# 1_power.net
KiCad netlist of a schematic drawn in Altium Designer
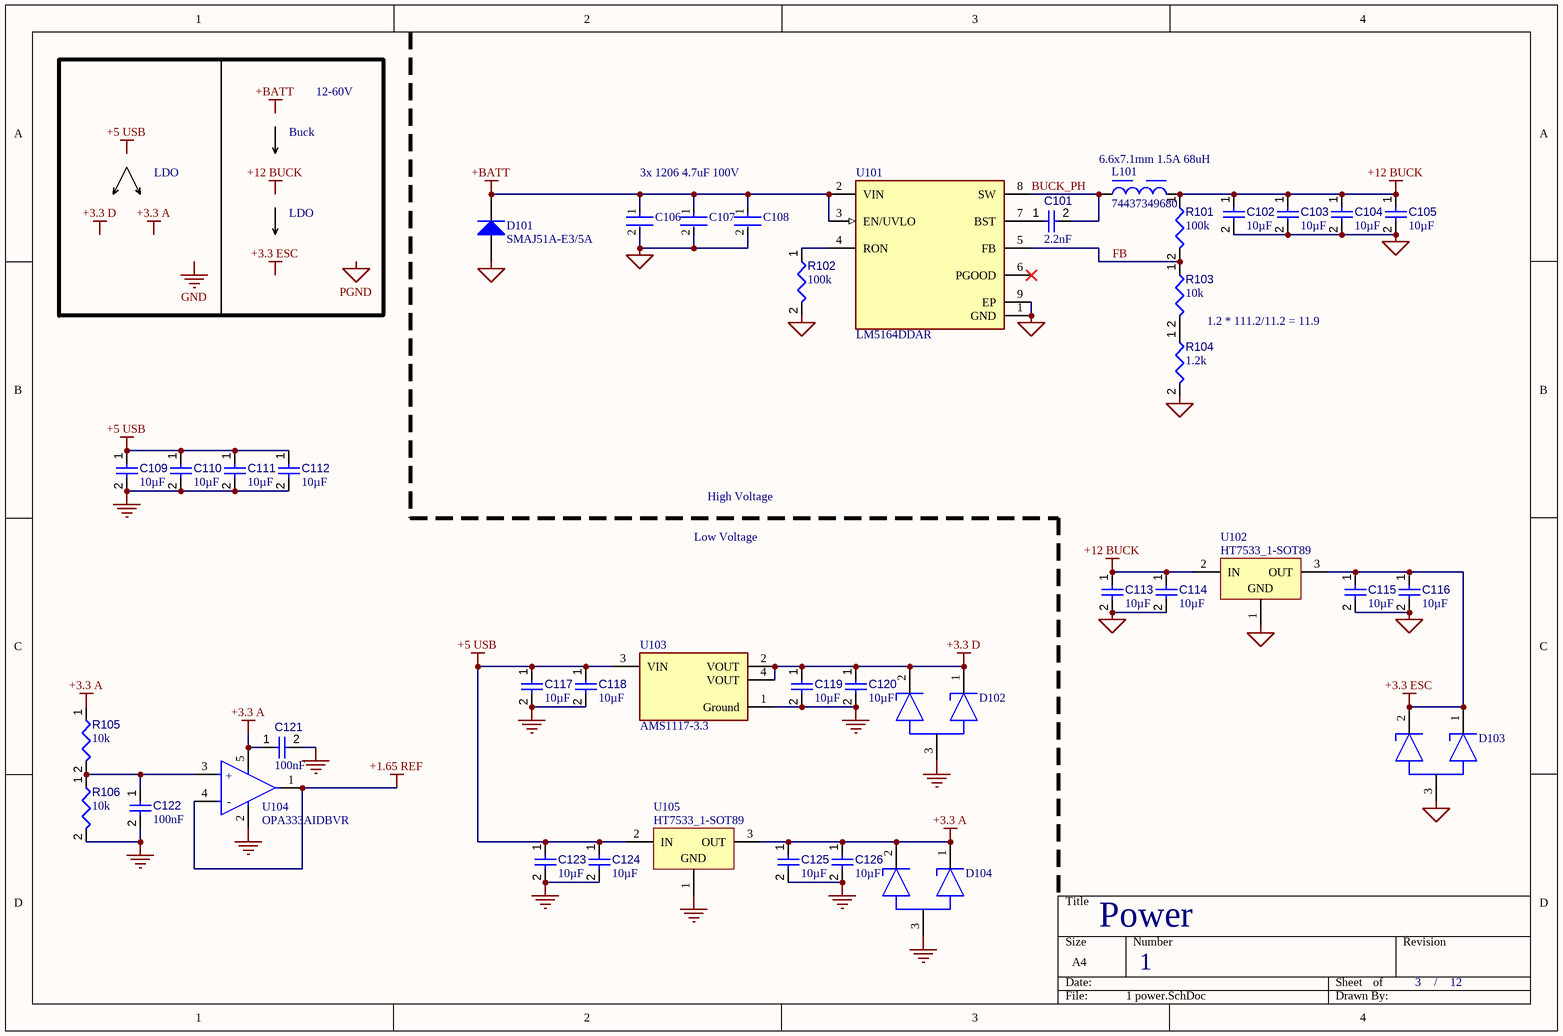
[diagram p0: 1 power.SchDoc]

(export (version "E")
  (design (tool "Eeschema 10.0.6"))
  (components
    (comp (ref "C101")
      (value "2.2nF")
      (footprint "CAPC0402(1005)33_L")
      (description "Chip Capacitor, 1nF +/-20%, 50V, 0402, Thickness 0.33 mm")
      (fields (field (name "TOLERANCE") "10%") (field (name "Comment") "Capacitor 2.2nF +/-20% 50V 0402"))
      (libsource (lib "UBC Uncrewed Aircraft Systems") (part "CAP-NP-2"))
    )
    (comp (ref "C102")
      (value "10µF")
      (footprint "CAPC0603(1608)100_L")
      (description "Chip Capacitor, 10µF +/-20%, 10V, 0603, Thickness 1 mm")
      (fields (field (name "TOLERANCE") "10%") (field (name "Comment") "Capacitor 10µF +/-20% 10V 0603"))
      (libsource (lib "UBC Uncrewed Aircraft Systems") (part "CAP-NP-2"))
    )
    (comp (ref "C103")
      (value "10µF")
      (footprint "CAPC0603(1608)100_L")
      (description "Chip Capacitor, 10µF +/-20%, 10V, 0603, Thickness 1 mm")
      (fields (field (name "TOLERANCE") "10%") (field (name "Comment") "Capacitor 10µF +/-20% 10V 0603"))
      (libsource (lib "UBC Uncrewed Aircraft Systems") (part "CAP-NP-2"))
    )
    (comp (ref "C104")
      (value "10µF")
      (footprint "CAPC0603(1608)100_L")
      (description "Chip Capacitor, 10µF +/-20%, 10V, 0603, Thickness 1 mm")
      (fields (field (name "TOLERANCE") "10%") (field (name "Comment") "Capacitor 10µF +/-20% 10V 0603"))
      (libsource (lib "UBC Uncrewed Aircraft Systems") (part "CAP-NP-2"))
    )
    (comp (ref "C105")
      (value "10µF")
      (footprint "CAPC0603(1608)100_L")
      (description "Chip Capacitor, 10µF +/-20%, 10V, 0603, Thickness 1 mm")
      (fields (field (name "TOLERANCE") "10%") (field (name "Comment") "Capacitor 10µF +/-20% 10V 0603"))
      (libsource (lib "UBC Uncrewed Aircraft Systems") (part "CAP-NP-2"))
    )
    (comp (ref "C106")
      (value "12061Z475KAT2A")
      (footprint "FP-1206-L_3_2_0_2-W_1_6_0-MFG")
      (description "CAP CER 4.7UF 100V X7S 1206")
      (fields (field (name "TOLERANCE") "10%"))
      (libsource (lib "Altium Content Vault") (part "b4654b650e69147ec39a6b967a45e02"))
    )
    (comp (ref "C107")
      (value "12061Z475KAT2A")
      (footprint "FP-1206-L_3_2_0_2-W_1_6_0-MFG")
      (description "CAP CER 4.7UF 100V X7S 1206")
      (fields (field (name "TOLERANCE") "10%"))
      (libsource (lib "Altium Content Vault") (part "b4654b650e69147ec39a6b967a45e02"))
    )
    (comp (ref "C108")
      (value "12061Z475KAT2A")
      (footprint "FP-1206-L_3_2_0_2-W_1_6_0-MFG")
      (description "CAP CER 4.7UF 100V X7S 1206")
      (fields (field (name "TOLERANCE") "10%"))
      (libsource (lib "Altium Content Vault") (part "b4654b650e69147ec39a6b967a45e02"))
    )
    (comp (ref "C109")
      (value "10µF")
      (footprint "CAPC0603(1608)100_L")
      (description "Chip Capacitor, 10µF +/-20%, 10V, 0603, Thickness 1 mm")
      (fields (field (name "TOLERANCE") "10%") (field (name "Comment") "Capacitor 10µF +/-20% 10V 0603"))
      (libsource (lib "UBC Uncrewed Aircraft Systems") (part "CAP-NP-2"))
    )
    (comp (ref "C110")
      (value "10µF")
      (footprint "CAPC0603(1608)100_L")
      (description "Chip Capacitor, 10µF +/-20%, 10V, 0603, Thickness 1 mm")
      (fields (field (name "TOLERANCE") "10%") (field (name "Comment") "Capacitor 10µF +/-20% 10V 0603"))
      (libsource (lib "UBC Uncrewed Aircraft Systems") (part "CAP-NP-2"))
    )
    (comp (ref "C111")
      (value "10µF")
      (footprint "CAPC0603(1608)100_L")
      (description "Chip Capacitor, 10µF +/-20%, 10V, 0603, Thickness 1 mm")
      (fields (field (name "TOLERANCE") "10%") (field (name "Comment") "Capacitor 10µF +/-20% 10V 0603"))
      (libsource (lib "UBC Uncrewed Aircraft Systems") (part "CAP-NP-2"))
    )
    (comp (ref "C112")
      (value "10µF")
      (footprint "CAPC0603(1608)100_L")
      (description "Chip Capacitor, 10µF +/-20%, 10V, 0603, Thickness 1 mm")
      (fields (field (name "TOLERANCE") "10%") (field (name "Comment") "Capacitor 10µF +/-20% 10V 0603"))
      (libsource (lib "UBC Uncrewed Aircraft Systems") (part "CAP-NP-2"))
    )
    (comp (ref "C113")
      (value "10µF")
      (footprint "CAPC0603(1608)100_L")
      (description "Chip Capacitor, 10µF +/-20%, 10V, 0603, Thickness 1 mm")
      (fields (field (name "TOLERANCE") "10%") (field (name "Comment") "Capacitor 10µF +/-20% 10V 0603"))
      (libsource (lib "UBC Uncrewed Aircraft Systems") (part "CAP-NP-2"))
    )
    (comp (ref "C114")
      (value "10µF")
      (footprint "CAPC0603(1608)100_L")
      (description "Chip Capacitor, 10µF +/-20%, 10V, 0603, Thickness 1 mm")
      (fields (field (name "TOLERANCE") "10%") (field (name "Comment") "Capacitor 10µF +/-20% 10V 0603"))
      (libsource (lib "UBC Uncrewed Aircraft Systems") (part "CAP-NP-2"))
    )
    (comp (ref "C115")
      (value "10µF")
      (footprint "CAPC0603(1608)100_L")
      (description "Chip Capacitor, 10µF +/-20%, 10V, 0603, Thickness 1 mm")
      (fields (field (name "TOLERANCE") "10%") (field (name "Comment") "Capacitor 10µF +/-20% 10V 0603"))
      (libsource (lib "UBC Uncrewed Aircraft Systems") (part "CAP-NP-2"))
    )
    (comp (ref "C116")
      (value "10µF")
      (footprint "CAPC0603(1608)100_L")
      (description "Chip Capacitor, 10µF +/-20%, 10V, 0603, Thickness 1 mm")
      (fields (field (name "TOLERANCE") "10%") (field (name "Comment") "Capacitor 10µF +/-20% 10V 0603"))
      (libsource (lib "UBC Uncrewed Aircraft Systems") (part "CAP-NP-2"))
    )
    (comp (ref "C117")
      (value "10µF")
      (footprint "CAPC0603(1608)100_L")
      (description "Chip Capacitor, 10µF +/-20%, 10V, 0603, Thickness 1 mm")
      (fields (field (name "TOLERANCE") "10%") (field (name "Comment") "Capacitor 10µF +/-20% 10V 0603"))
      (libsource (lib "UBC Uncrewed Aircraft Systems") (part "CAP-NP-2"))
    )
    (comp (ref "C118")
      (value "10µF")
      (footprint "CAPC0603(1608)100_L")
      (description "Chip Capacitor, 10µF +/-20%, 10V, 0603, Thickness 1 mm")
      (fields (field (name "TOLERANCE") "10%") (field (name "Comment") "Capacitor 10µF +/-20% 10V 0603"))
      (libsource (lib "UBC Uncrewed Aircraft Systems") (part "CAP-NP-2"))
    )
    (comp (ref "C119")
      (value "10µF")
      (footprint "CAPC0603(1608)100_L")
      (description "Chip Capacitor, 10µF +/-20%, 10V, 0603, Thickness 1 mm")
      (fields (field (name "TOLERANCE") "10%") (field (name "Comment") "Capacitor 10µF +/-20% 10V 0603"))
      (libsource (lib "UBC Uncrewed Aircraft Systems") (part "CAP-NP-2"))
    )
    (comp (ref "C120")
      (value "10µF")
      (footprint "CAPC0603(1608)100_L")
      (description "Chip Capacitor, 10µF +/-20%, 10V, 0603, Thickness 1 mm")
      (fields (field (name "TOLERANCE") "10%") (field (name "Comment") "Capacitor 10µF +/-20% 10V 0603"))
      (libsource (lib "UBC Uncrewed Aircraft Systems") (part "CAP-NP-2"))
    )
    (comp (ref "C121")
      (value "100nF")
      (footprint "CAPC0402(1005)60_L")
      (description "Chip Capacitor, 100nF +/-20%, 25V, 0402, Thickness 0.6 mm")
      (fields (field (name "TOLERANCE") "10%") (field (name "Comment") "Capacitor 100nF +/-20% 25V 0402"))
      (libsource (lib "UBC Uncrewed Aircraft Systems") (part "CAP-NP-2"))
    )
    (comp (ref "C122")
      (value "100nF")
      (footprint "CAPC0402(1005)60_L")
      (description "Chip Capacitor, 100nF +/-20%, 25V, 0402, Thickness 0.6 mm")
      (fields (field (name "TOLERANCE") "10%") (field (name "Comment") "Capacitor 100nF +/-20% 25V 0402"))
      (libsource (lib "UBC Uncrewed Aircraft Systems") (part "CAP-NP-2"))
    )
    (comp (ref "C123")
      (value "10µF")
      (footprint "CAPC0603(1608)100_L")
      (description "Chip Capacitor, 10µF +/-20%, 10V, 0603, Thickness 1 mm")
      (fields (field (name "TOLERANCE") "10%") (field (name "Comment") "Capacitor 10µF +/-20% 10V 0603"))
      (libsource (lib "UBC Uncrewed Aircraft Systems") (part "CAP-NP-2"))
    )
    (comp (ref "C124")
      (value "10µF")
      (footprint "CAPC0603(1608)100_L")
      (description "Chip Capacitor, 10µF +/-20%, 10V, 0603, Thickness 1 mm")
      (fields (field (name "TOLERANCE") "10%") (field (name "Comment") "Capacitor 10µF +/-20% 10V 0603"))
      (libsource (lib "UBC Uncrewed Aircraft Systems") (part "CAP-NP-2"))
    )
    (comp (ref "C125")
      (value "10µF")
      (footprint "CAPC0603(1608)100_L")
      (description "Chip Capacitor, 10µF +/-20%, 10V, 0603, Thickness 1 mm")
      (fields (field (name "TOLERANCE") "10%") (field (name "Comment") "Capacitor 10µF +/-20% 10V 0603"))
      (libsource (lib "UBC Uncrewed Aircraft Systems") (part "CAP-NP-2"))
    )
    (comp (ref "C126")
      (value "10µF")
      (footprint "CAPC0603(1608)100_L")
      (description "Chip Capacitor, 10µF +/-20%, 10V, 0603, Thickness 1 mm")
      (fields (field (name "TOLERANCE") "10%") (field (name "Comment") "Capacitor 10µF +/-20% 10V 0603"))
      (libsource (lib "UBC Uncrewed Aircraft Systems") (part "CAP-NP-2"))
    )
    (comp (ref "D101")
      (value "SMAJ51A-E3/5A")
      (footprint "VISH-DO-214AC-2_N")
      (fields (field (name "MANUFACTURER") "Vishay Semiconductor"))
      (libsource (lib "Altium Content Vault") (part "VISH-K1A2-2"))
    )
    (comp (ref "D102")
      (value "PESD3V3S2UT,215")
      (footprint "FP-SOT23-IPC_A")
      (description "TVS DIODE 3.3VWM 20VC TO236AB")
      (libsource (lib "Altium Content Vault") (part "05bab3e457e9f60b0f1ca7a96343362"))
    )
    (comp (ref "D103")
      (value "PESD3V3S2UT,215")
      (footprint "FP-SOT23-IPC_A")
      (description "TVS DIODE 3.3VWM 20VC TO236AB")
      (libsource (lib "Altium Content Vault") (part "05bab3e457e9f60b0f1ca7a96343362"))
    )
    (comp (ref "D104")
      (value "PESD3V3S2UT,215")
      (footprint "FP-SOT23-IPC_A")
      (description "TVS DIODE 3.3VWM 20VC TO236AB")
      (libsource (lib "Altium Content Vault") (part "05bab3e457e9f60b0f1ca7a96343362"))
    )
    (comp (ref "L101")
      (value "74437349680")
      (footprint "WE-LHMI_7050")
      (libsource (lib "Altium Content Vault") (part "Inductor - 3"))
    )
    (comp (ref "R101")
      (value "100k")
      (footprint "RESC0402(1005)_L")
      (description "Chip Resistor, 100 kOhms, +/-1 %, 63 mW, -55 to 155 degC, 0402")
      (fields (field (name "TOLERANCE") "1%") (field (name "POWER") "63mW"))
      (libsource (lib "UBC Uncrewed Aircraft Systems") (part "RES-2"))
    )
    (comp (ref "R102")
      (value "100k")
      (footprint "RESC0402(1005)_L")
      (description "Chip Resistor, 100 kOhms, +/-1 %, 63 mW, -55 to 155 degC, 0402")
      (fields (field (name "TOLERANCE") "1%") (field (name "POWER") "63mW"))
      (libsource (lib "UBC Uncrewed Aircraft Systems") (part "RES-2"))
    )
    (comp (ref "R103")
      (value "10k")
      (footprint "RESC0402(1005)_L")
      (description "Chip Resistor, 10 kOhms, +/-1 %, 63 mW, -55 to 125 degC, 0402")
      (fields (field (name "POWER") "63mW") (field (name "TOLERANCE") "1%"))
      (libsource (lib "UBC Uncrewed Aircraft Systems") (part "RES-2"))
    )
    (comp (ref "R104")
      (value "1.2k")
      (footprint "RESC0402(1005)_L")
      (description "Chip Resistor, 1.2 kOhms, +/-1 %, 63 mW, -55 to 155 degC, 0402")
      (fields (field (name "TOLERANCE") "1%") (field (name "POWER") "63mW"))
      (libsource (lib "UBC Uncrewed Aircraft Systems") (part "RES-2"))
    )
    (comp (ref "R105")
      (value "10k")
      (footprint "RESC0402(1005)_L")
      (description "Chip Resistor, 10 kOhms, +/-1 %, 63 mW, -55 to 125 degC, 0402")
      (fields (field (name "POWER") "63mW") (field (name "TOLERANCE") "1%"))
      (libsource (lib "UBC Uncrewed Aircraft Systems") (part "RES-2"))
    )
    (comp (ref "R106")
      (value "10k")
      (footprint "RESC0402(1005)_L")
      (description "Chip Resistor, 10 kOhms, +/-1 %, 63 mW, -55 to 125 degC, 0402")
      (fields (field (name "POWER") "63mW") (field (name "TOLERANCE") "1%"))
      (libsource (lib "UBC Uncrewed Aircraft Systems") (part "RES-2"))
    )
    (comp (ref "U101")
      (value "LM5164DDAR")
      (footprint "FP-DDA0008E-MFG")
      (description "POWER MANAGEMENT")
      (fields
        (field (name "MANUFACTURER") "Texas Instruments")
        (field (name "OCTOPART") "https://octopart.com/lm5164ddar-texas+instruments-96785744")
      )
      (libsource (lib "Altium Content Vault") (part "ad4762e8767f3654d2dc1ed5c3dee12"))
    )
    (comp (ref "U102")
      (value "HT7533_1-SOT89")
      (footprint "SOT89_L")
      (description "100mA Low Power LDO, Output Voltage 3.3V, SOT89 Pkg")
      (libsource (lib "Altium Content Vault") (part "PM-REG-HT75xx-1-IL3"))
    )
    (comp (ref "U103")
      (value "AMS1117-3.3")
      (footprint "FP-AMS1117-IPC_C")
      (description "LDO Voltage Regulators 1A, 3.3V")
      (fields
        (field (name "OCTOPART") "https://octopart.com/ams1117-3.3-advanced+monolithic+systems-25899300")
        (field (name "MANUFACTURER") "Advanced Monolithic Systems")
      )
      (libsource (lib "Altium Content Vault") (part "8bdbb5f8e77002000e30dd2845d0354"))
    )
    (comp (ref "U104")
      (value "OPA333AIDBVR")
      (footprint "FP-DBV0005A-MFG")
      (description "IC OPAMP ZER-DRIFT 1CIRC SOT23-5")
      (libsource (lib "Altium Content Vault") (part "1dcd28e651784f0a5a8ed6f8452eeff"))
    )
    (comp (ref "U105")
      (value "HT7533_1-SOT89")
      (footprint "SOT89_L")
      (description "100mA Low Power LDO, Output Voltage 3.3V, SOT89 Pkg")
      (libsource (lib "Altium Content Vault") (part "PM-REG-HT75xx-1-IL3"))
    )
  )
  (nets
    (net (code "1") (name "+1.65 REF") (class "Default")
      (node (ref "U104") (pin "1") (pinfunction "OUT_1") (pintype "passive"))
      (node (ref "U104") (pin "4") (pinfunction "-IN_4") (pintype "tri_state"))
    )
    (net (code "2") (name "+3.3 A") (class "Default")
      (node (ref "C121") (pin "1") (pinfunction "1_1") (pintype "passive"))
      (node (ref "C125") (pin "1") (pinfunction "1_1") (pintype "passive"))
      (node (ref "C126") (pin "1") (pinfunction "1_1") (pintype "passive"))
      (node (ref "D104") (pin "1") (pinfunction "1_1") (pintype "passive"))
      (node (ref "D104") (pin "2") (pinfunction "2_2") (pintype "passive"))
      (node (ref "R105") (pin "1") (pinfunction "1_1") (pintype "passive"))
      (node (ref "U104") (pin "5") (pinfunction "V+_5") (pintype "power_in"))
      (node (ref "U105") (pin "3") (pinfunction "OUT_3") (pintype "power_in"))
    )
    (net (code "3") (name "+3.3 D") (class "Default")
      (node (ref "C119") (pin "1") (pinfunction "1_1") (pintype "passive"))
      (node (ref "C120") (pin "1") (pinfunction "1_1") (pintype "passive"))
      (node (ref "D102") (pin "1") (pinfunction "1_1") (pintype "passive"))
      (node (ref "D102") (pin "2") (pinfunction "2_2") (pintype "passive"))
      (node (ref "U103") (pin "2") (pinfunction "VOUT_2") (pintype "passive"))
      (node (ref "U103") (pin "4") (pinfunction "VOUT_4") (pintype "passive"))
    )
    (net (code "4") (name "+3.3 ESC") (class "Default")
      (node (ref "C115") (pin "1") (pinfunction "1_1") (pintype "passive"))
      (node (ref "C116") (pin "1") (pinfunction "1_1") (pintype "passive"))
      (node (ref "D103") (pin "1") (pinfunction "1_1") (pintype "passive"))
      (node (ref "D103") (pin "2") (pinfunction "2_2") (pintype "passive"))
      (node (ref "U102") (pin "3") (pinfunction "OUT_3") (pintype "power_in"))
    )
    (net (code "5") (name "+5 USB") (class "Default")
      (node (ref "C109") (pin "1") (pinfunction "1_1") (pintype "passive"))
      (node (ref "C110") (pin "1") (pinfunction "1_1") (pintype "passive"))
      (node (ref "C111") (pin "1") (pinfunction "1_1") (pintype "passive"))
      (node (ref "C112") (pin "1") (pinfunction "1_1") (pintype "passive"))
      (node (ref "C117") (pin "1") (pinfunction "1_1") (pintype "passive"))
      (node (ref "C118") (pin "1") (pinfunction "1_1") (pintype "passive"))
      (node (ref "C123") (pin "1") (pinfunction "1_1") (pintype "passive"))
      (node (ref "C124") (pin "1") (pinfunction "1_1") (pintype "passive"))
      (node (ref "U103") (pin "3") (pinfunction "VIN_3") (pintype "power_in"))
      (node (ref "U105") (pin "2") (pinfunction "IN_2") (pintype "power_in"))
    )
    (net (code "6") (name "+12 BUCK") (class "Default")
      (node (ref "C102") (pin "1") (pinfunction "1_1") (pintype "passive"))
      (node (ref "C103") (pin "1") (pinfunction "1_1") (pintype "passive"))
      (node (ref "C104") (pin "1") (pinfunction "1_1") (pintype "passive"))
      (node (ref "C105") (pin "1") (pinfunction "1_1") (pintype "passive"))
      (node (ref "C113") (pin "1") (pinfunction "1_1") (pintype "passive"))
      (node (ref "C114") (pin "1") (pinfunction "1_1") (pintype "passive"))
      (node (ref "L101") (pin "2") (pinfunction "2_2") (pintype "passive"))
      (node (ref "R101") (pin "1") (pinfunction "1_1") (pintype "passive"))
      (node (ref "U102") (pin "2") (pinfunction "IN_2") (pintype "power_in"))
    )
    (net (code "7") (name "+BATT") (class "Default")
      (node (ref "C106") (pin "1") (pinfunction "1_1") (pintype "passive"))
      (node (ref "C107") (pin "1") (pinfunction "1_1") (pintype "passive"))
      (node (ref "C108") (pin "1") (pinfunction "1_1") (pintype "passive"))
      (node (ref "D101") (pin "1") (pinfunction "K_1") (pintype "passive"))
      (node (ref "U101") (pin "2") (pinfunction "VIN_2") (pintype "power_in"))
      (node (ref "U101") (pin "3") (pinfunction "EN/UVLO_3") (pintype "input"))
    )
    (net (code "8") (name "/BUCK_PH") (class "Default")
      (node (ref "C101") (pin "2") (pinfunction "2_2") (pintype "passive"))
      (node (ref "L101") (pin "1") (pinfunction "1_1") (pintype "passive"))
      (node (ref "U101") (pin "8") (pinfunction "SW_8") (pintype "passive"))
    )
    (net (code "9") (name "/FB") (class "Default")
      (node (ref "R101") (pin "2") (pinfunction "2_2") (pintype "passive"))
      (node (ref "R103") (pin "1") (pinfunction "1_1") (pintype "passive"))
      (node (ref "U101") (pin "5") (pinfunction "FB_5") (pintype "passive"))
    )
    (net (code "10") (name "GND") (class "Default")
      (node (ref "C109") (pin "2") (pinfunction "2_2") (pintype "passive"))
      (node (ref "C110") (pin "2") (pinfunction "2_2") (pintype "passive"))
      (node (ref "C111") (pin "2") (pinfunction "2_2") (pintype "passive"))
      (node (ref "C112") (pin "2") (pinfunction "2_2") (pintype "passive"))
      (node (ref "C117") (pin "2") (pinfunction "2_2") (pintype "passive"))
      (node (ref "C118") (pin "2") (pinfunction "2_2") (pintype "passive"))
      (node (ref "C119") (pin "2") (pinfunction "2_2") (pintype "passive"))
      (node (ref "C120") (pin "2") (pinfunction "2_2") (pintype "passive"))
      (node (ref "C121") (pin "2") (pinfunction "2_2") (pintype "passive"))
      (node (ref "C122") (pin "2") (pinfunction "2_2") (pintype "passive"))
      (node (ref "C123") (pin "2") (pinfunction "2_2") (pintype "passive"))
      (node (ref "C124") (pin "2") (pinfunction "2_2") (pintype "passive"))
      (node (ref "C125") (pin "2") (pinfunction "2_2") (pintype "passive"))
      (node (ref "C126") (pin "2") (pinfunction "2_2") (pintype "passive"))
      (node (ref "D102") (pin "3") (pinfunction "3_3") (pintype "passive"))
      (node (ref "D104") (pin "3") (pinfunction "3_3") (pintype "passive"))
      (node (ref "R106") (pin "2") (pinfunction "2_2") (pintype "passive"))
      (node (ref "U103") (pin "1") (pinfunction "Ground_1") (pintype "power_in"))
      (node (ref "U104") (pin "2") (pinfunction "V-_2") (pintype "power_in"))
      (node (ref "U105") (pin "1") (pinfunction "GND_1") (pintype "power_in"))
    )
    (net (code "11") (name "Net-(R103-Pad2)") (class "Default")
      (node (ref "R103") (pin "2") (pinfunction "2_2") (pintype "passive"))
      (node (ref "R104") (pin "1") (pinfunction "1_1") (pintype "passive"))
    )
    (net (code "12") (name "Net-(U101-BST)") (class "Default")
      (node (ref "C101") (pin "1") (pinfunction "1_1") (pintype "passive"))
      (node (ref "U101") (pin "7") (pinfunction "BST_7") (pintype "passive"))
    )
    (net (code "13") (name "Net-(U101-RON)") (class "Default")
      (node (ref "R102") (pin "1") (pinfunction "1_1") (pintype "passive"))
      (node (ref "U101") (pin "4") (pinfunction "RON_4") (pintype "passive"))
    )
    (net (code "14") (name "Net-(U104-+IN)") (class "Default")
      (node (ref "C122") (pin "1") (pinfunction "1_1") (pintype "passive"))
      (node (ref "R105") (pin "2") (pinfunction "2_2") (pintype "passive"))
      (node (ref "R106") (pin "1") (pinfunction "1_1") (pintype "passive"))
      (node (ref "U104") (pin "3") (pinfunction "+IN_3") (pintype "tri_state"))
    )
    (net (code "15") (name "PGND") (class "Default")
      (node (ref "C102") (pin "2") (pinfunction "2_2") (pintype "passive"))
      (node (ref "C103") (pin "2") (pinfunction "2_2") (pintype "passive"))
      (node (ref "C104") (pin "2") (pinfunction "2_2") (pintype "passive"))
      (node (ref "C105") (pin "2") (pinfunction "2_2") (pintype "passive"))
      (node (ref "C106") (pin "2") (pinfunction "2_2") (pintype "passive"))
      (node (ref "C107") (pin "2") (pinfunction "2_2") (pintype "passive"))
      (node (ref "C108") (pin "2") (pinfunction "2_2") (pintype "passive"))
      (node (ref "C113") (pin "2") (pinfunction "2_2") (pintype "passive"))
      (node (ref "C114") (pin "2") (pinfunction "2_2") (pintype "passive"))
      (node (ref "C115") (pin "2") (pinfunction "2_2") (pintype "passive"))
      (node (ref "C116") (pin "2") (pinfunction "2_2") (pintype "passive"))
      (node (ref "D101") (pin "2") (pinfunction "A_2") (pintype "passive"))
      (node (ref "D103") (pin "3") (pinfunction "3_3") (pintype "passive"))
      (node (ref "R102") (pin "2") (pinfunction "2_2") (pintype "passive"))
      (node (ref "R104") (pin "2") (pinfunction "2_2") (pintype "passive"))
      (node (ref "U101") (pin "1") (pinfunction "GND_1") (pintype "power_in"))
      (node (ref "U101") (pin "9") (pinfunction "EP_9") (pintype "passive"))
      (node (ref "U102") (pin "1") (pinfunction "GND_1") (pintype "power_in"))
    )
    (net (code "16") (name "unconnected-(U101-PGOOD-Pad6)") (class "Default")
      (node (ref "U101") (pin "6") (pinfunction "PGOOD_6") (pintype "open_collector+no_connect"))
    )
  )
)
